# schematic.net
KiCad netlist of a schematic drawn in EasyEDA
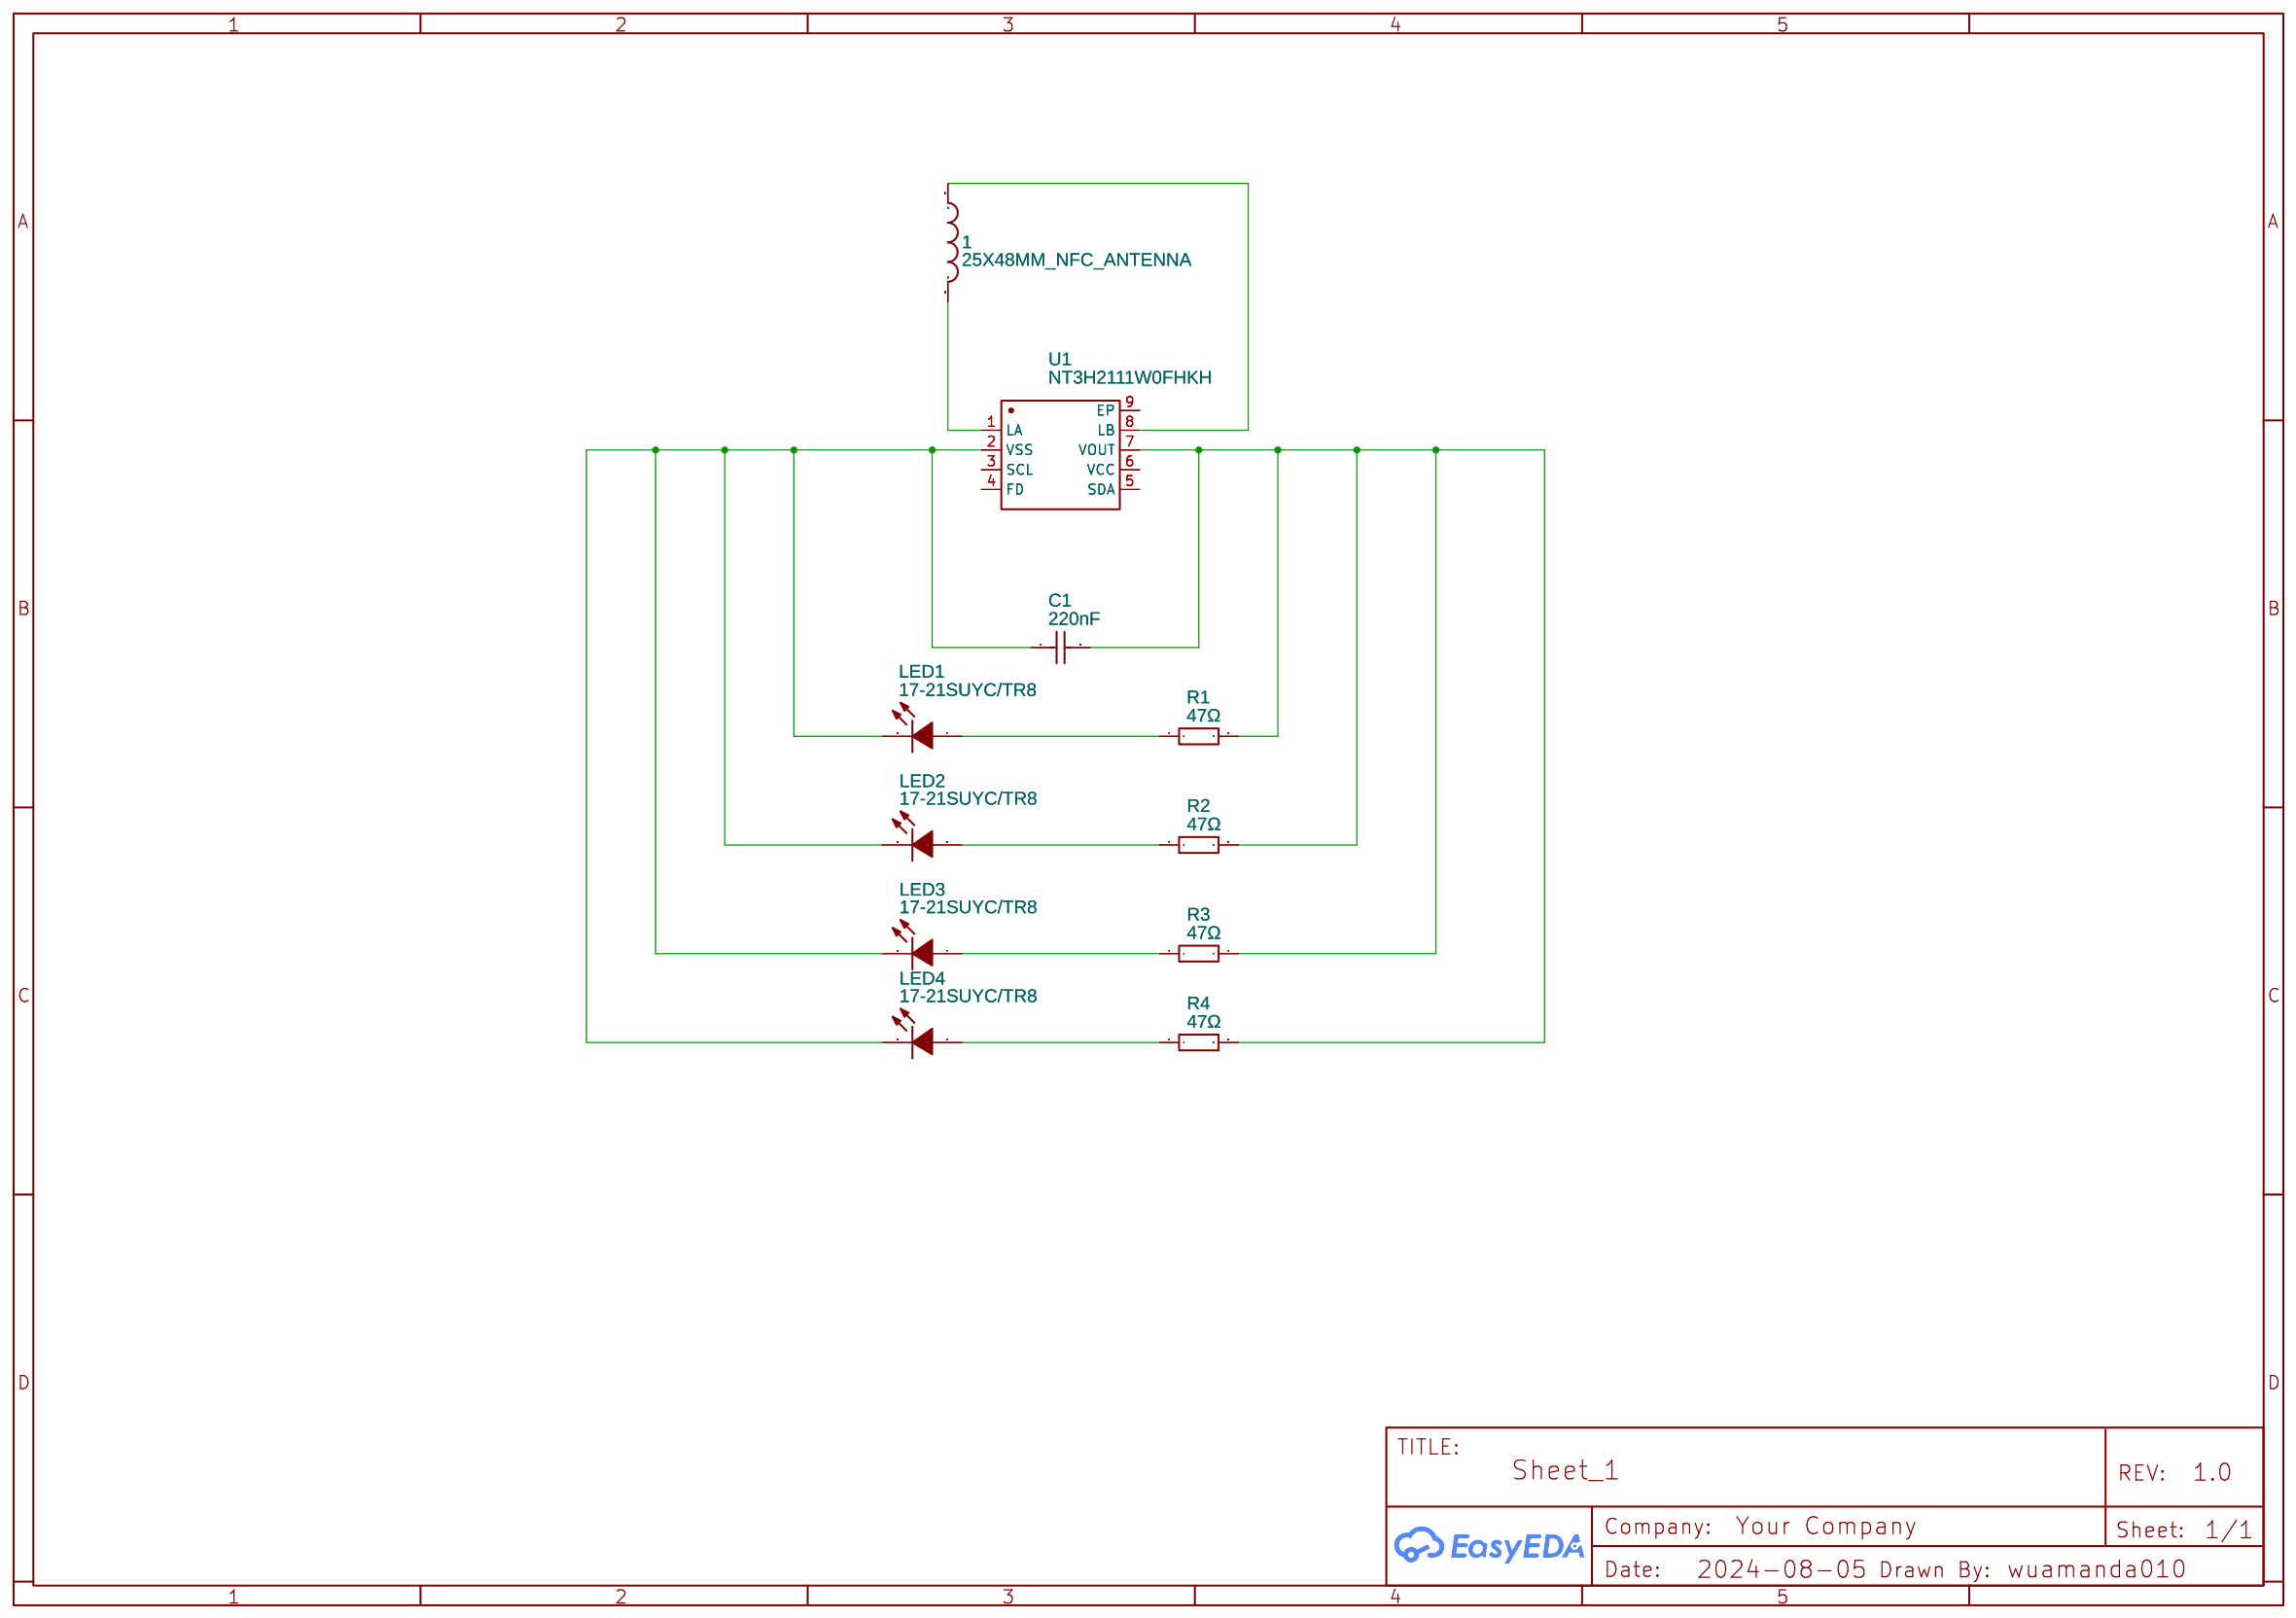
[diagram p0: schematic sheet]

(export (version "E")
  (design (tool "Eeschema 10.0.6"))
  (components
    (comp (ref "1") (value "25X48MM_NFC_ANTENNA") (libsource (lib "") (part "25X48MM_NFC_ANTENNA")))
    (comp (ref "C1")
      (value "220nF")
      (fields
        (field (name "Manufacturer Part") "CL10B224KA8NNNC")
        (field (name "Manufacturer") "SAMSUNG(三星)")
      )
      (libsource (lib "") (part "CL10B224KA8NNNC"))
    )
    (comp (ref "LED1")
      (value "17-21SUYC/TR8")
      (fields (field (name "Manufacturer Part") "KT-0805黄灯") (field (name "Manufacturer") "KENTO"))
      (libsource (lib "") (part "17-21SUYC/TR8"))
    )
    (comp (ref "LED2")
      (value "17-21SUYC/TR8")
      (fields (field (name "Manufacturer Part") "KT-0805黄灯") (field (name "Manufacturer") "KENTO"))
      (libsource (lib "") (part "17-21SUYC/TR8"))
    )
    (comp (ref "LED3")
      (value "17-21SUYC/TR8")
      (fields (field (name "Manufacturer Part") "KT-0805黄灯") (field (name "Manufacturer") "KENTO"))
      (libsource (lib "") (part "17-21SUYC/TR8"))
    )
    (comp (ref "LED4")
      (value "17-21SUYC/TR8")
      (fields (field (name "Manufacturer Part") "KT-0805黄灯") (field (name "Manufacturer") "KENTO"))
      (libsource (lib "") (part "17-21SUYC/TR8"))
    )
    (comp (ref "R1")
      (value "47Ω")
      (fields
        (field (name "Manufacturer Part") "0603WAF470JT5E")
        (field (name "Manufacturer") "UNI-ROYAL(厚声)")
      )
      (libsource (lib "") (part "0603WAF470JT5E"))
    )
    (comp (ref "R2")
      (value "47Ω")
      (fields
        (field (name "Manufacturer Part") "0603WAF470JT5E")
        (field (name "Manufacturer") "UNI-ROYAL(厚声)")
      )
      (libsource (lib "") (part "0603WAF470JT5E"))
    )
    (comp (ref "R3")
      (value "47Ω")
      (fields
        (field (name "Manufacturer Part") "0603WAF470JT5E")
        (field (name "Manufacturer") "UNI-ROYAL(厚声)")
      )
      (libsource (lib "") (part "0603WAF470JT5E"))
    )
    (comp (ref "R4")
      (value "47Ω")
      (fields
        (field (name "Manufacturer Part") "0603WAF470JT5E")
        (field (name "Manufacturer") "UNI-ROYAL(厚声)")
      )
      (libsource (lib "") (part "0603WAF470JT5E"))
    )
    (comp (ref "U1")
      (value "NT3H2111W0FHKH")
      (fields (field (name "Manufacturer") "NXP(恩智浦)"))
      (libsource (lib "") (part "NT3H2111W0FHKH"))
    )
  )
  (nets
    (net (code "1") (name "Net-(LED1-+)") (class "Default")
      (node (ref "LED1") (pin "1") (pinfunction "+_1") (pintype "unspecified"))
      (node (ref "R1") (pin "1") (pinfunction "1_1") (pintype "input"))
    )
    (net (code "2") (name "Net-(LED1--)") (class "Default")
      (node (ref "C1") (pin "1") (pinfunction "1_1") (pintype "input"))
      (node (ref "LED1") (pin "2") (pinfunction "-_2") (pintype "unspecified"))
      (node (ref "LED2") (pin "2") (pinfunction "-_2") (pintype "unspecified"))
      (node (ref "LED3") (pin "2") (pinfunction "-_2") (pintype "unspecified"))
      (node (ref "LED4") (pin "2") (pinfunction "-_2") (pintype "unspecified"))
      (node (ref "U1") (pin "2") (pinfunction "VSS_2") (pintype "unspecified"))
    )
    (net (code "3") (name "Net-(LED2-+)") (class "Default")
      (node (ref "LED2") (pin "1") (pinfunction "+_1") (pintype "unspecified"))
      (node (ref "R2") (pin "1") (pinfunction "1_1") (pintype "input"))
    )
    (net (code "4") (name "Net-(LED3-+)") (class "Default")
      (node (ref "LED3") (pin "1") (pinfunction "+_1") (pintype "unspecified"))
      (node (ref "R3") (pin "1") (pinfunction "1_1") (pintype "input"))
    )
    (net (code "5") (name "Net-(LED4-+)") (class "Default")
      (node (ref "LED4") (pin "1") (pinfunction "+_1") (pintype "unspecified"))
      (node (ref "R4") (pin "1") (pinfunction "1_1") (pintype "input"))
    )
    (net (code "6") (name "Net-(U1-LA)") (class "Default")
      (node (ref "1") (pin "P$2") (pinfunction "P$2_P$2") (pintype "bidirectional"))
      (node (ref "U1") (pin "1") (pinfunction "LA_1") (pintype "unspecified"))
    )
    (net (code "7") (name "Net-(U1-LB)") (class "Default")
      (node (ref "1") (pin "P$1") (pinfunction "P$1_P$1") (pintype "bidirectional"))
      (node (ref "U1") (pin "8") (pinfunction "LB_8") (pintype "unspecified"))
    )
    (net (code "8") (name "Net-(U1-VOUT)") (class "Default")
      (node (ref "C1") (pin "2") (pinfunction "2_2") (pintype "input"))
      (node (ref "R1") (pin "2") (pinfunction "2_2") (pintype "input"))
      (node (ref "R2") (pin "2") (pinfunction "2_2") (pintype "input"))
      (node (ref "R3") (pin "2") (pinfunction "2_2") (pintype "input"))
      (node (ref "R4") (pin "2") (pinfunction "2_2") (pintype "input"))
      (node (ref "U1") (pin "7") (pinfunction "VOUT_7") (pintype "unspecified"))
    )
    (net (code "9") (name "unconnected-(U1-EP-Pad9)") (class "Default")
      (node (ref "U1") (pin "9") (pinfunction "EP_9") (pintype "unspecified"))
    )
    (net (code "10") (name "unconnected-(U1-FD-Pad4)") (class "Default")
      (node (ref "U1") (pin "4") (pinfunction "FD_4") (pintype "unspecified"))
    )
    (net (code "11") (name "unconnected-(U1-SCL-Pad3)") (class "Default")
      (node (ref "U1") (pin "3") (pinfunction "SCL_3") (pintype "unspecified"))
    )
    (net (code "12") (name "unconnected-(U1-SDA-Pad5)") (class "Default")
      (node (ref "U1") (pin "5") (pinfunction "SDA_5") (pintype "unspecified"))
    )
    (net (code "13") (name "unconnected-(U1-VCC-Pad6)") (class "Default")
      (node (ref "U1") (pin "6") (pinfunction "VCC_6") (pintype "unspecified"))
    )
  )
)
